# siguelineas.net
KiCad netlist of a schematic drawn in EAGLE
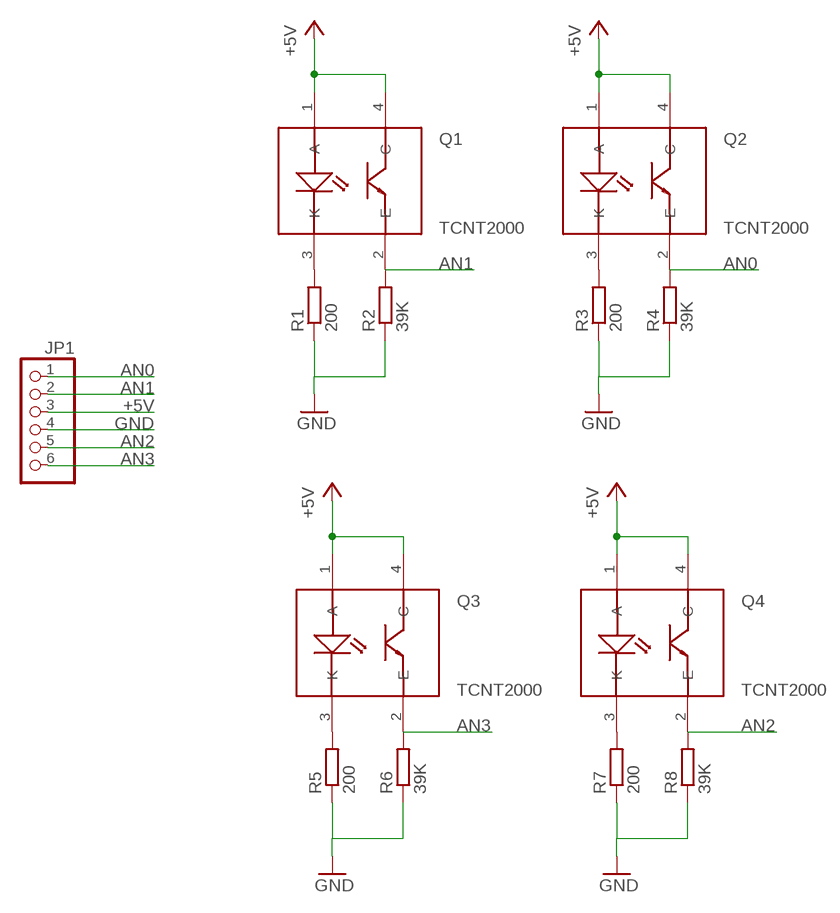
[diagram p0: schematic, sheet 1]

(export (version "E")
  (design (tool "Eeschema 10.0.6"))
  (components
    (comp (ref "JP1")
      (value "PINHD-1X6")
      (footprint "eagle-import:1X06")
      (libsource (lib "eagle-import") (part "PINHD-1X6"))
    )
    (comp (ref "Q1")
      (value "TCNT2000")
      (footprint "eagle-import:SMD")
      (libsource (lib "eagle-import") (part "TCNT2000"))
    )
    (comp (ref "Q2")
      (value "TCNT2000")
      (footprint "eagle-import:SMD")
      (libsource (lib "eagle-import") (part "TCNT2000"))
    )
    (comp (ref "Q3")
      (value "TCNT2000")
      (footprint "eagle-import:SMD")
      (libsource (lib "eagle-import") (part "TCNT2000"))
    )
    (comp (ref "Q4")
      (value "TCNT2000")
      (footprint "eagle-import:SMD")
      (libsource (lib "eagle-import") (part "TCNT2000"))
    )
    (comp (ref "R1")
      (value "200")
      (footprint "eagle-import:R0805")
      (libsource (lib "eagle-import") (part "R-EU_R0805"))
    )
    (comp (ref "R2")
      (value "39K")
      (footprint "eagle-import:R0805")
      (libsource (lib "eagle-import") (part "R-EU_R0805"))
    )
    (comp (ref "R3")
      (value "200")
      (footprint "eagle-import:R0805")
      (libsource (lib "eagle-import") (part "R-EU_R0805"))
    )
    (comp (ref "R4")
      (value "39K")
      (footprint "eagle-import:R0805")
      (libsource (lib "eagle-import") (part "R-EU_R0805"))
    )
    (comp (ref "R5")
      (value "200")
      (footprint "eagle-import:R0805")
      (libsource (lib "eagle-import") (part "R-EU_R0805"))
    )
    (comp (ref "R6")
      (value "39K")
      (footprint "eagle-import:R0805")
      (libsource (lib "eagle-import") (part "R-EU_R0805"))
    )
    (comp (ref "R7")
      (value "200")
      (footprint "eagle-import:R0805")
      (libsource (lib "eagle-import") (part "R-EU_R0805"))
    )
    (comp (ref "R8")
      (value "39K")
      (footprint "eagle-import:R0805")
      (libsource (lib "eagle-import") (part "R-EU_R0805"))
    )
  )
  (nets
    (net (code "1") (name "+5V") (class "Default")
      (node (ref "JP1") (pin "3") (pinfunction "3_3") (pintype "passive"))
      (node (ref "Q1") (pin "1") (pinfunction "A_1") (pintype "bidirectional"))
      (node (ref "Q1") (pin "4") (pinfunction "C_4") (pintype "bidirectional"))
      (node (ref "Q2") (pin "1") (pinfunction "A_1") (pintype "bidirectional"))
      (node (ref "Q2") (pin "4") (pinfunction "C_4") (pintype "bidirectional"))
      (node (ref "Q3") (pin "1") (pinfunction "A_1") (pintype "bidirectional"))
      (node (ref "Q3") (pin "4") (pinfunction "C_4") (pintype "bidirectional"))
      (node (ref "Q4") (pin "1") (pinfunction "A_1") (pintype "bidirectional"))
      (node (ref "Q4") (pin "4") (pinfunction "C_4") (pintype "bidirectional"))
    )
    (net (code "2") (name "/AN0") (class "Default")
      (node (ref "JP1") (pin "1") (pinfunction "1_1") (pintype "passive"))
      (node (ref "Q2") (pin "2") (pinfunction "E_2") (pintype "bidirectional"))
      (node (ref "R4") (pin "2") (pinfunction "2_2") (pintype "passive"))
    )
    (net (code "3") (name "/AN1") (class "Default")
      (node (ref "JP1") (pin "2") (pinfunction "2_2") (pintype "passive"))
      (node (ref "Q1") (pin "2") (pinfunction "E_2") (pintype "bidirectional"))
      (node (ref "R2") (pin "2") (pinfunction "2_2") (pintype "passive"))
    )
    (net (code "4") (name "/AN2") (class "Default")
      (node (ref "JP1") (pin "5") (pinfunction "5_5") (pintype "passive"))
      (node (ref "Q4") (pin "2") (pinfunction "E_2") (pintype "bidirectional"))
      (node (ref "R8") (pin "2") (pinfunction "2_2") (pintype "passive"))
    )
    (net (code "5") (name "/AN3") (class "Default")
      (node (ref "JP1") (pin "6") (pinfunction "6_6") (pintype "passive"))
      (node (ref "Q3") (pin "2") (pinfunction "E_2") (pintype "bidirectional"))
      (node (ref "R6") (pin "2") (pinfunction "2_2") (pintype "passive"))
    )
    (net (code "6") (name "GND") (class "Default")
      (node (ref "JP1") (pin "4") (pinfunction "4_4") (pintype "passive"))
      (node (ref "R1") (pin "1") (pinfunction "1_1") (pintype "passive"))
      (node (ref "R2") (pin "1") (pinfunction "1_1") (pintype "passive"))
      (node (ref "R3") (pin "1") (pinfunction "1_1") (pintype "passive"))
      (node (ref "R4") (pin "1") (pinfunction "1_1") (pintype "passive"))
      (node (ref "R5") (pin "1") (pinfunction "1_1") (pintype "passive"))
      (node (ref "R6") (pin "1") (pinfunction "1_1") (pintype "passive"))
      (node (ref "R7") (pin "1") (pinfunction "1_1") (pintype "passive"))
      (node (ref "R8") (pin "1") (pinfunction "1_1") (pintype "passive"))
    )
    (net (code "7") (name "Net-(Q1-K)") (class "Default")
      (node (ref "Q1") (pin "3") (pinfunction "K_3") (pintype "bidirectional"))
      (node (ref "R1") (pin "2") (pinfunction "2_2") (pintype "passive"))
    )
    (net (code "8") (name "Net-(Q2-K)") (class "Default")
      (node (ref "Q2") (pin "3") (pinfunction "K_3") (pintype "bidirectional"))
      (node (ref "R3") (pin "2") (pinfunction "2_2") (pintype "passive"))
    )
    (net (code "9") (name "Net-(Q3-K)") (class "Default")
      (node (ref "Q3") (pin "3") (pinfunction "K_3") (pintype "bidirectional"))
      (node (ref "R5") (pin "2") (pinfunction "2_2") (pintype "passive"))
    )
    (net (code "10") (name "Net-(Q4-K)") (class "Default")
      (node (ref "Q4") (pin "3") (pinfunction "K_3") (pintype "bidirectional"))
      (node (ref "R7") (pin "2") (pinfunction "2_2") (pintype "passive"))
    )
  )
)
